# Interface.net
KiCad netlist of a schematic drawn in Altium Designer
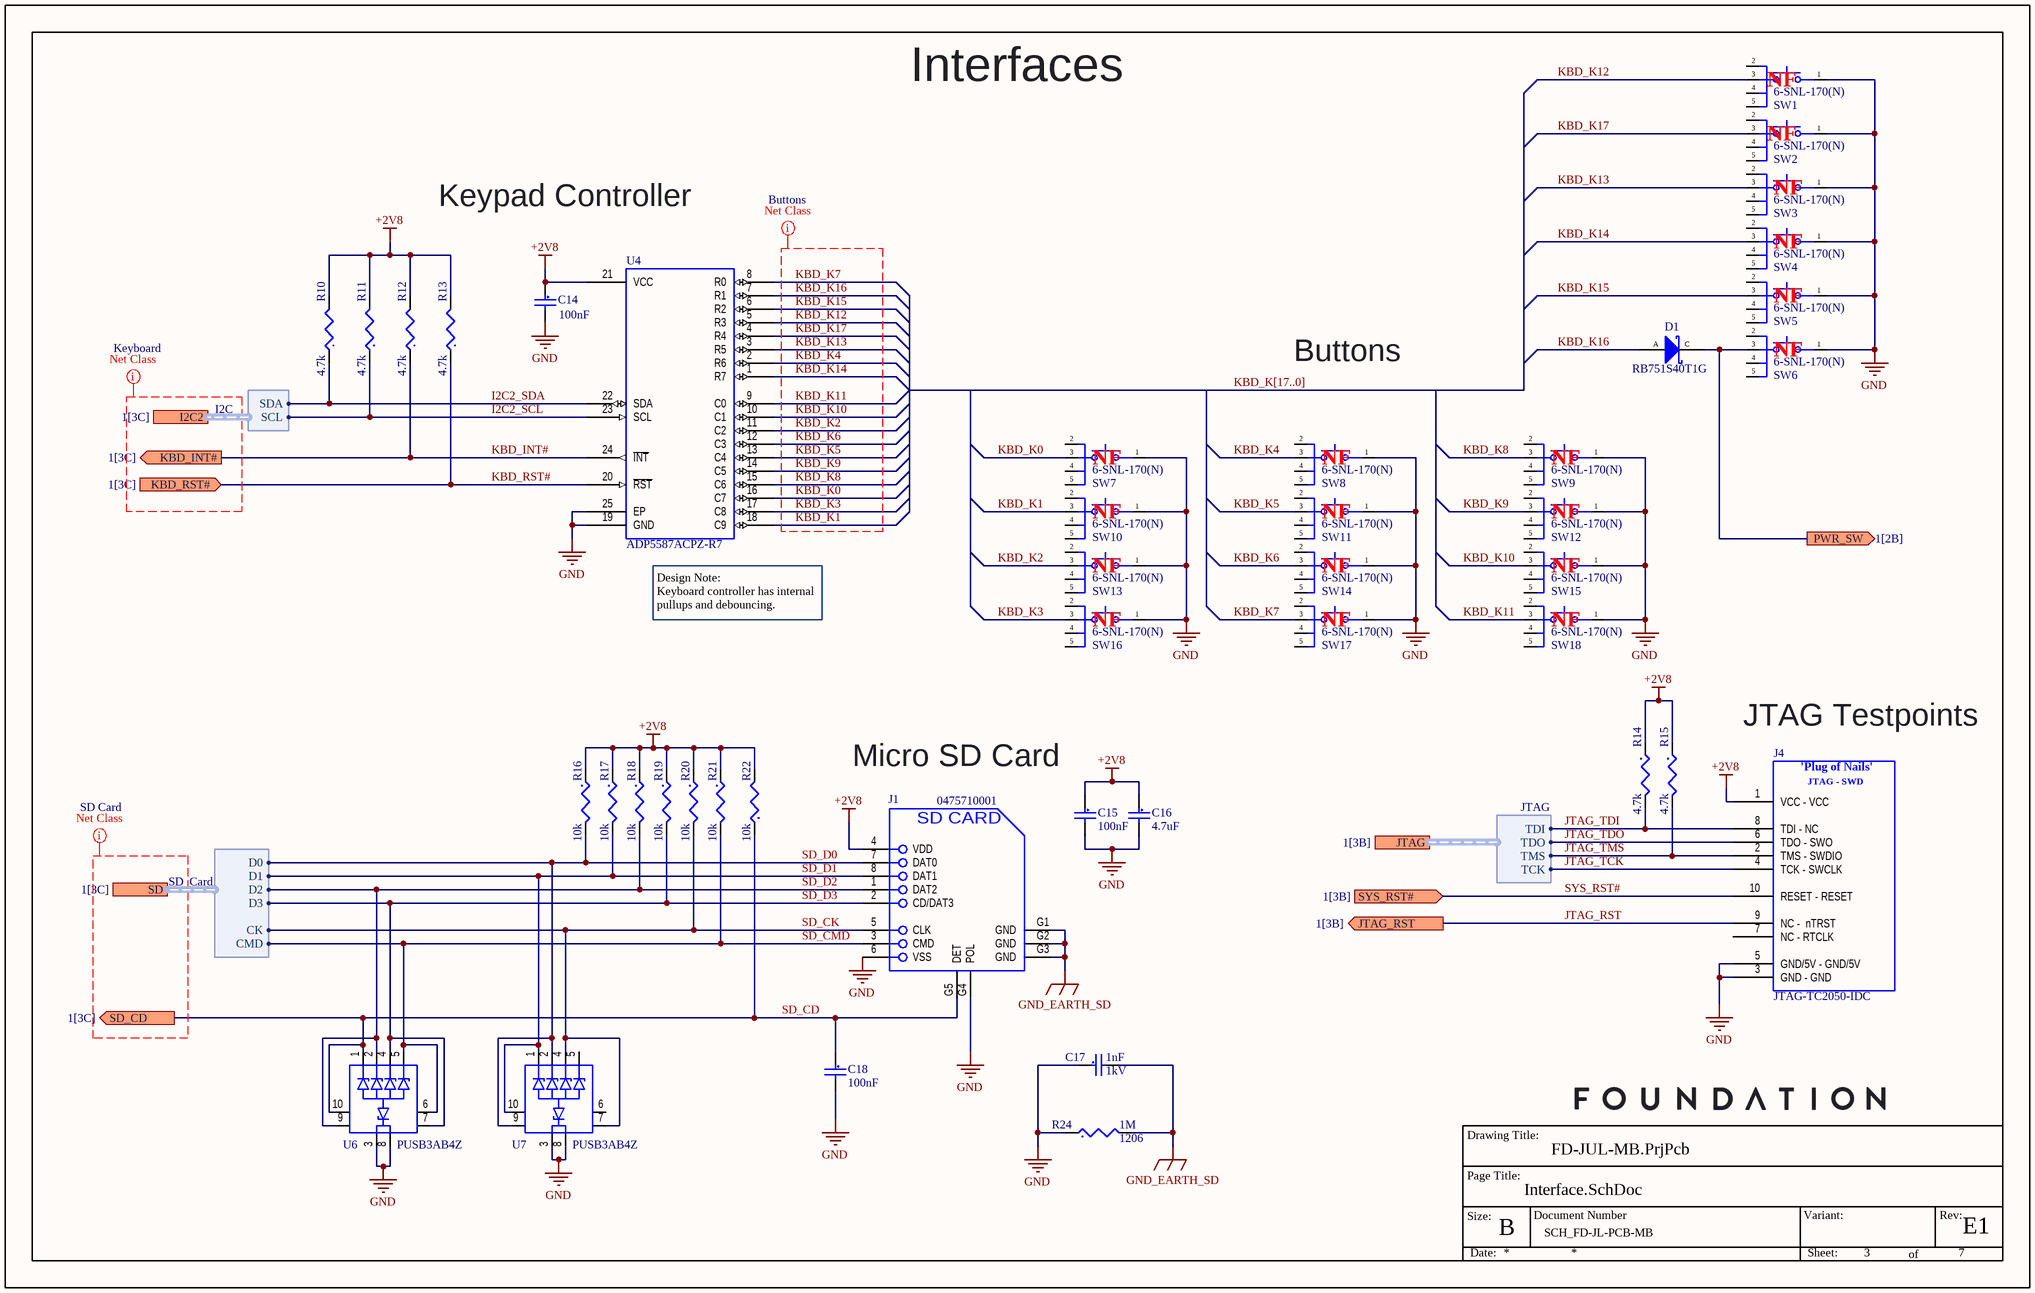
[diagram p0: Interface.SchDoc]

(export (version "E")
  (design (tool "Eeschema 10.0.6"))
  (components
    (comp (ref "C14")
      (value "CAP CER 0.1uF 16V 10% X7R 0402")
      (footprint "CAPC0402(1005)55_L")
      (description "0.1µF ±10% 16V Ceramic Capacitor X7R 0402 (1005 Metric)")
      (fields
        (field (name "CAPACITANCE") "100nF")
        (field (name "TOLERANCE") "10%")
        (field (name "VOLTAGE") "16V")
      )
      (libsource (lib "Altium Concord Pro on A365") (part "CAP-NP-2"))
    )
    (comp (ref "C15")
      (value "CAP CER 0.1uF 16V 10% X7R 0402")
      (footprint "CAPC0402(1005)55_L")
      (description "0.1µF ±10% 16V Ceramic Capacitor X7R 0402 (1005 Metric)")
      (fields
        (field (name "CAPACITANCE") "100nF")
        (field (name "TOLERANCE") "10%")
        (field (name "VOLTAGE") "16V")
      )
      (libsource (lib "Altium Concord Pro on A365") (part "CAP-NP-2"))
    )
    (comp (ref "C16")
      (value "CAP CER 4.7uF 16V 10% X5R 0603")
      (footprint "CAPC0603(1608)90_L")
      (description "4.7µF ±10% 16V Ceramic Capacitor X5R 0603 (1608 Metric)")
      (fields (field (name "CAPACITANCE") "4.7uF") (field (name "TOLERANCE") "10%"))
      (libsource (lib "Altium Concord Pro on A365") (part "CAP-NP-2"))
    )
    (comp (ref "C17")
      (value "CAP CER 1000pF 1000V 10% X7R 0805")
      (footprint "CAPC0805(2012)145_N")
      (description "1000pF ±10% 1000V (1kV) Ceramic Capacitor X7R 0805 (2012 Metric)")
      (fields
        (field (name "CAPACITANCE") "1nF")
        (field (name "VOLTAGE RATING (DC)") "1kV")
        (field (name "TOLERANCE") "10%")
      )
      (libsource (lib "Altium Concord Pro on A365") (part "CAP-NP-2"))
    )
    (comp (ref "C18")
      (value "CAP CER 0.1uF 16V 10% X7R 0402")
      (footprint "CAPC0402(1005)55_L")
      (description "0.1µF ±10% 16V Ceramic Capacitor X7R 0402 (1005 Metric)")
      (fields
        (field (name "CAPACITANCE") "100nF")
        (field (name "TOLERANCE") "10%")
        (field (name "VOLTAGE") "16V")
      )
      (libsource (lib "Altium Concord Pro on A365") (part "CAP-NP-2"))
    )
    (comp (ref "D1")
      (value "RB751S40T1G")
      (footprint "ON - SOD-523_V")
      (description "Diode Schottky 30V 30mA (DC) Surface Mount SOD-523")
      (libsource (lib "Altium Concord Pro on A365") (part "DSKY-AC-2"))
    )
    (comp (ref "J1")
      (value "0475710001")
      (footprint "MOLX - 0475710001_V")
      (description "CONN MICRO SD CARD PUSH-PULL R/A")
      (libsource (lib "Altium Concord Pro on A365") (part "CN-SD-0475710001"))
    )
    (comp (ref "J4")
      (value "JTAG-TC2050-IDC")
      (footprint "TAGC - TC2050-IDC-FP_V")
      (description "PLUG-OF-NAILS 10-PIN W/LEGS")
      (libsource (lib "Altium Concord Pro on A365") (part "JTAG-TC2050-IDC"))
    )
    (comp (ref "R10")
      (value "RES 4.7K 1/16W 1% 0402")
      (footprint "RESC0402(1005)_L")
      (description "4.7 kOhms ±1% 0.063W, 1/16W Chip Resistor 0402 (1005 Metric) Automotive AEC-Q200 Thick Film")
      (fields (field (name "RESISTANCE") "4.7k") (field (name "TOLERANCE") "1%"))
      (libsource (lib "Altium Concord Pro on A365") (part "RES-2"))
    )
    (comp (ref "R11")
      (value "RES 4.7K 1/16W 1% 0402")
      (footprint "RESC0402(1005)_L")
      (description "4.7 kOhms ±1% 0.063W, 1/16W Chip Resistor 0402 (1005 Metric) Automotive AEC-Q200 Thick Film")
      (fields (field (name "RESISTANCE") "4.7k") (field (name "TOLERANCE") "1%"))
      (libsource (lib "Altium Concord Pro on A365") (part "RES-2"))
    )
    (comp (ref "R12")
      (value "RES 4.7K 1/16W 1% 0402")
      (footprint "RESC0402(1005)_L")
      (description "4.7 kOhms ±1% 0.063W, 1/16W Chip Resistor 0402 (1005 Metric) Automotive AEC-Q200 Thick Film")
      (fields (field (name "RESISTANCE") "4.7k") (field (name "TOLERANCE") "1%"))
      (libsource (lib "Altium Concord Pro on A365") (part "RES-2"))
    )
    (comp (ref "R13")
      (value "RES 4.7K 1/16W 1% 0402")
      (footprint "RESC0402(1005)_L")
      (description "4.7 kOhms ±1% 0.063W, 1/16W Chip Resistor 0402 (1005 Metric) Automotive AEC-Q200 Thick Film")
      (fields (field (name "RESISTANCE") "4.7k") (field (name "TOLERANCE") "1%"))
      (libsource (lib "Altium Concord Pro on A365") (part "RES-2"))
    )
    (comp (ref "R14")
      (value "RES 4.7K 1/16W 1% 0402")
      (footprint "RESC0402(1005)_L")
      (description "4.7 kOhms ±1% 0.063W, 1/16W Chip Resistor 0402 (1005 Metric) Automotive AEC-Q200 Thick Film")
      (fields (field (name "RESISTANCE") "4.7k") (field (name "TOLERANCE") "1%"))
      (libsource (lib "Altium Concord Pro on A365") (part "RES-2"))
    )
    (comp (ref "R15")
      (value "RES 4.7K 1/16W 1% 0402")
      (footprint "RESC0402(1005)_L")
      (description "4.7 kOhms ±1% 0.063W, 1/16W Chip Resistor 0402 (1005 Metric) Automotive AEC-Q200 Thick Film")
      (fields (field (name "RESISTANCE") "4.7k") (field (name "TOLERANCE") "1%"))
      (libsource (lib "Altium Concord Pro on A365") (part "RES-2"))
    )
    (comp (ref "R16")
      (value "RES 10K 1/16W 1% 0402")
      (footprint "RESC0402(1005)_L")
      (description "10 kOhms ±1% 0.063W, 1/16W Chip Resistor 0402 (1005 Metric)")
      (fields (field (name "RESISTANCE") "10k") (field (name "TOLERANCE") "1%"))
      (libsource (lib "Altium Concord Pro on A365") (part "RES-2"))
    )
    (comp (ref "R17")
      (value "RES 10K 1/16W 1% 0402")
      (footprint "RESC0402(1005)_L")
      (description "10 kOhms ±1% 0.063W, 1/16W Chip Resistor 0402 (1005 Metric)")
      (fields (field (name "RESISTANCE") "10k") (field (name "TOLERANCE") "1%"))
      (libsource (lib "Altium Concord Pro on A365") (part "RES-2"))
    )
    (comp (ref "R18")
      (value "RES 10K 1/16W 1% 0402")
      (footprint "RESC0402(1005)_L")
      (description "10 kOhms ±1% 0.063W, 1/16W Chip Resistor 0402 (1005 Metric)")
      (fields (field (name "RESISTANCE") "10k") (field (name "TOLERANCE") "1%"))
      (libsource (lib "Altium Concord Pro on A365") (part "RES-2"))
    )
    (comp (ref "R19")
      (value "RES 10K 1/16W 1% 0402")
      (footprint "RESC0402(1005)_L")
      (description "10 kOhms ±1% 0.063W, 1/16W Chip Resistor 0402 (1005 Metric)")
      (fields (field (name "RESISTANCE") "10k") (field (name "TOLERANCE") "1%"))
      (libsource (lib "Altium Concord Pro on A365") (part "RES-2"))
    )
    (comp (ref "R20")
      (value "RES 10K 1/16W 1% 0402")
      (footprint "RESC0402(1005)_L")
      (description "10 kOhms ±1% 0.063W, 1/16W Chip Resistor 0402 (1005 Metric)")
      (fields (field (name "RESISTANCE") "10k") (field (name "TOLERANCE") "1%"))
      (libsource (lib "Altium Concord Pro on A365") (part "RES-2"))
    )
    (comp (ref "R21")
      (value "RES 10K 1/16W 1% 0402")
      (footprint "RESC0402(1005)_L")
      (description "10 kOhms ±1% 0.063W, 1/16W Chip Resistor 0402 (1005 Metric)")
      (fields (field (name "RESISTANCE") "10k") (field (name "TOLERANCE") "1%"))
      (libsource (lib "Altium Concord Pro on A365") (part "RES-2"))
    )
    (comp (ref "R22")
      (value "RES 10K 1/16W 1% 0402")
      (footprint "RESC0402(1005)_L")
      (description "10 kOhms ±1% 0.063W, 1/16W Chip Resistor 0402 (1005 Metric)")
      (fields (field (name "RESISTANCE") "10k") (field (name "TOLERANCE") "1%"))
      (libsource (lib "Altium Concord Pro on A365") (part "RES-2"))
    )
    (comp (ref "R24")
      (value "RES 1.0M 1/4W 5% 1206")
      (footprint "RESC1206(3216)_L")
      (description "1 MOhms ±5% 0.25W, 1/4W Chip Resistor 1206 (3216 Metric) Moisture Resistant Thick Film")
      (fields
        (field (name "RESISTANCE") "1M")
        (field (name "TOLERANCE") "5%")
        (field (name "CASE CODE (IMPERIAL)") "1206")
      )
      (libsource (lib "Altium Concord Pro on A365") (part "RES-2"))
    )
    (comp (ref "SW1")
      (value "6-SNL-170(N)")
      (footprint "TACT - 6-SNL-170_NTP_V")
      (description "Tactile Components. 6mm star dome tactile switch.")
      (libsource (lib "Altium Concord Pro on A365") (part "TAC-2-4"))
    )
    (comp (ref "SW2")
      (value "6-SNL-170(N)")
      (footprint "TACT - 6-SNL-170_NTP_V")
      (description "Tactile Components. 6mm star dome tactile switch.")
      (libsource (lib "Altium Concord Pro on A365") (part "TAC-2-4"))
    )
    (comp (ref "SW3")
      (value "6-SNL-170(N)")
      (footprint "TACT - 6-SNL-170_NTP_V")
      (description "Tactile Components. 6mm star dome tactile switch.")
      (libsource (lib "Altium Concord Pro on A365") (part "TAC-2-4"))
    )
    (comp (ref "SW4")
      (value "6-SNL-170(N)")
      (footprint "TACT - 6-SNL-170_NTP_V")
      (description "Tactile Components. 6mm star dome tactile switch.")
      (libsource (lib "Altium Concord Pro on A365") (part "TAC-2-4"))
    )
    (comp (ref "SW5")
      (value "6-SNL-170(N)")
      (footprint "TACT - 6-SNL-170_NTP_V")
      (description "Tactile Components. 6mm star dome tactile switch.")
      (libsource (lib "Altium Concord Pro on A365") (part "TAC-2-4"))
    )
    (comp (ref "SW6")
      (value "6-SNL-170(N)")
      (footprint "TACT - 6-SNL-170_NTP_V")
      (description "Tactile Components. 6mm star dome tactile switch.")
      (libsource (lib "Altium Concord Pro on A365") (part "TAC-2-4"))
    )
    (comp (ref "SW7")
      (value "6-SNL-170(N)")
      (footprint "TACT - 6-SNL-170_NTP_V")
      (description "Tactile Components. 6mm star dome tactile switch.")
      (libsource (lib "Altium Concord Pro on A365") (part "TAC-2-4"))
    )
    (comp (ref "SW8")
      (value "6-SNL-170(N)")
      (footprint "TACT - 6-SNL-170_NTP_V")
      (description "Tactile Components. 6mm star dome tactile switch.")
      (libsource (lib "Altium Concord Pro on A365") (part "TAC-2-4"))
    )
    (comp (ref "SW9")
      (value "6-SNL-170(N)")
      (footprint "TACT - 6-SNL-170_NTP_V")
      (description "Tactile Components. 6mm star dome tactile switch.")
      (libsource (lib "Altium Concord Pro on A365") (part "TAC-2-4"))
    )
    (comp (ref "SW10")
      (value "6-SNL-170(N)")
      (footprint "TACT - 6-SNL-170_NTP_V")
      (description "Tactile Components. 6mm star dome tactile switch.")
      (libsource (lib "Altium Concord Pro on A365") (part "TAC-2-4"))
    )
    (comp (ref "SW11")
      (value "6-SNL-170(N)")
      (footprint "TACT - 6-SNL-170_NTP_V")
      (description "Tactile Components. 6mm star dome tactile switch.")
      (libsource (lib "Altium Concord Pro on A365") (part "TAC-2-4"))
    )
    (comp (ref "SW12")
      (value "6-SNL-170(N)")
      (footprint "TACT - 6-SNL-170_NTP_V")
      (description "Tactile Components. 6mm star dome tactile switch.")
      (libsource (lib "Altium Concord Pro on A365") (part "TAC-2-4"))
    )
    (comp (ref "SW13")
      (value "6-SNL-170(N)")
      (footprint "TACT - 6-SNL-170_NTP_V")
      (description "Tactile Components. 6mm star dome tactile switch.")
      (libsource (lib "Altium Concord Pro on A365") (part "TAC-2-4"))
    )
    (comp (ref "SW14")
      (value "6-SNL-170(N)")
      (footprint "TACT - 6-SNL-170_NTP_V")
      (description "Tactile Components. 6mm star dome tactile switch.")
      (libsource (lib "Altium Concord Pro on A365") (part "TAC-2-4"))
    )
    (comp (ref "SW15")
      (value "6-SNL-170(N)")
      (footprint "TACT - 6-SNL-170_NTP_V")
      (description "Tactile Components. 6mm star dome tactile switch.")
      (libsource (lib "Altium Concord Pro on A365") (part "TAC-2-4"))
    )
    (comp (ref "SW16")
      (value "6-SNL-170(N)")
      (footprint "TACT - 6-SNL-170_NTP_V")
      (description "Tactile Components. 6mm star dome tactile switch.")
      (libsource (lib "Altium Concord Pro on A365") (part "TAC-2-4"))
    )
    (comp (ref "SW17")
      (value "6-SNL-170(N)")
      (footprint "TACT - 6-SNL-170_NTP_V")
      (description "Tactile Components. 6mm star dome tactile switch.")
      (libsource (lib "Altium Concord Pro on A365") (part "TAC-2-4"))
    )
    (comp (ref "SW18")
      (value "6-SNL-170(N)")
      (footprint "TACT - 6-SNL-170_NTP_V")
      (description "Tactile Components. 6mm star dome tactile switch.")
      (libsource (lib "Altium Concord Pro on A365") (part "TAC-2-4"))
    )
    (comp (ref "U4")
      (value "ADP5587ACPZ-R7")
      (footprint "ADEV - LFCSP-24_L")
      (description "I/O Expander 18 I²C 400kHz 24-LFCSP-WQ (4x4)")
      (libsource (lib "Altium Concord Pro on A365") (part "ADP5587ACPZ"))
    )
    (comp (ref "U6")
      (value "PUSB3AB4Z")
      (footprint "NEXP - DFN2510A-10_L")
      (description "TVS DIODE 3.3V 5V DFN2510A-10")
      (libsource (lib "Altium Concord Pro on A365") (part "DTVS-ARY-4-1245-8-10"))
    )
    (comp (ref "U7")
      (value "PUSB3AB4Z")
      (footprint "NEXP - DFN2510A-10_L")
      (description "TVS DIODE 3.3V 5V DFN2510A-10")
      (libsource (lib "Altium Concord Pro on A365") (part "DTVS-ARY-4-1245-8-10"))
    )
  )
  (nets
    (net (code "4") (name "+2V8") (class "Default")
      (node (ref "C14") (pin "1") (pinfunction "1_1") (pintype "passive"))
      (node (ref "C15") (pin "1") (pinfunction "1_1") (pintype "passive"))
      (node (ref "C16") (pin "1") (pinfunction "1_1") (pintype "passive"))
      (node (ref "J1") (pin "4") (pinfunction "VDD_4") (pintype "passive"))
      (node (ref "J4") (pin "1") (pinfunction "VCC_-_VCC_1") (pintype "passive"))
      (node (ref "R10") (pin "2") (pinfunction "2_2") (pintype "passive"))
      (node (ref "R11") (pin "2") (pinfunction "2_2") (pintype "passive"))
      (node (ref "R12") (pin "2") (pinfunction "2_2") (pintype "passive"))
      (node (ref "R13") (pin "2") (pinfunction "2_2") (pintype "passive"))
      (node (ref "R14") (pin "1") (pinfunction "1_1") (pintype "passive"))
      (node (ref "R15") (pin "1") (pinfunction "1_1") (pintype "passive"))
      (node (ref "R16") (pin "1") (pinfunction "1_1") (pintype "passive"))
      (node (ref "R17") (pin "1") (pinfunction "1_1") (pintype "passive"))
      (node (ref "R18") (pin "1") (pinfunction "1_1") (pintype "passive"))
      (node (ref "R19") (pin "1") (pinfunction "1_1") (pintype "passive"))
      (node (ref "R20") (pin "1") (pinfunction "1_1") (pintype "passive"))
      (node (ref "R21") (pin "1") (pinfunction "1_1") (pintype "passive"))
      (node (ref "R22") (pin "2") (pinfunction "2_2") (pintype "passive"))
      (node (ref "U4") (pin "21") (pinfunction "VCC_21") (pintype "power_in"))
    )
    (net (code "5") (name "/I2C2_SCL") (class "Default")
      (node (ref "R11") (pin "1") (pinfunction "1_1") (pintype "passive"))
      (node (ref "U4") (pin "23") (pinfunction "SCL_23") (pintype "input"))
    )
    (net (code "6") (name "/I2C2_SDA") (class "Default")
      (node (ref "R10") (pin "1") (pinfunction "1_1") (pintype "passive"))
      (node (ref "U4") (pin "22") (pinfunction "SDA_22") (pintype "bidirectional"))
    )
    (net (code "7") (name "/JTAG_RST") (class "Default")
      (node (ref "J4") (pin "9") (pinfunction "NC_-__nTRST_9") (pintype "passive"))
    )
    (net (code "8") (name "/JTAG_TCK") (class "Default")
      (node (ref "J4") (pin "4") (pinfunction "TCK_-_SWCLK_4") (pintype "passive"))
    )
    (net (code "9") (name "/JTAG_TDI") (class "Default")
      (node (ref "J4") (pin "8") (pinfunction "TDI_-_NC_8") (pintype "passive"))
      (node (ref "R14") (pin "2") (pinfunction "2_2") (pintype "passive"))
    )
    (net (code "10") (name "/JTAG_TDO") (class "Default")
      (node (ref "J4") (pin "6") (pinfunction "TDO_-_SWO_6") (pintype "passive"))
    )
    (net (code "11") (name "/JTAG_TMS") (class "Default")
      (node (ref "J4") (pin "2") (pinfunction "TMS_-_SWDIO_2") (pintype "passive"))
      (node (ref "R15") (pin "2") (pinfunction "2_2") (pintype "passive"))
    )
    (net (code "12") (name "/KBD_INT#") (class "Default")
      (node (ref "R12") (pin "1") (pinfunction "1_1") (pintype "passive"))
      (node (ref "U4") (pin "24") (pinfunction "~{INT}_24") (pintype "output"))
    )
    (net (code "13") (name "/KBD_K0") (class "Default")
      (node (ref "SW7") (pin "3") (pinfunction "3_3") (pintype "passive"))
      (node (ref "U4") (pin "16") (pinfunction "C7_16") (pintype "bidirectional"))
    )
    (net (code "14") (name "/KBD_K1") (class "Default")
      (node (ref "SW10") (pin "3") (pinfunction "3_3") (pintype "passive"))
      (node (ref "U4") (pin "18") (pinfunction "C9_18") (pintype "bidirectional"))
    )
    (net (code "15") (name "/KBD_K2") (class "Default")
      (node (ref "SW13") (pin "3") (pinfunction "3_3") (pintype "passive"))
      (node (ref "U4") (pin "11") (pinfunction "C2_11") (pintype "bidirectional"))
    )
    (net (code "16") (name "/KBD_K3") (class "Default")
      (node (ref "SW16") (pin "3") (pinfunction "3_3") (pintype "passive"))
      (node (ref "U4") (pin "17") (pinfunction "C8_17") (pintype "bidirectional"))
    )
    (net (code "17") (name "/KBD_K4") (class "Default")
      (node (ref "SW8") (pin "3") (pinfunction "3_3") (pintype "passive"))
      (node (ref "U4") (pin "2") (pinfunction "R6_2") (pintype "bidirectional"))
    )
    (net (code "18") (name "/KBD_K5") (class "Default")
      (node (ref "SW11") (pin "3") (pinfunction "3_3") (pintype "passive"))
      (node (ref "U4") (pin "13") (pinfunction "C4_13") (pintype "bidirectional"))
    )
    (net (code "19") (name "/KBD_K6") (class "Default")
      (node (ref "SW14") (pin "3") (pinfunction "3_3") (pintype "passive"))
      (node (ref "U4") (pin "12") (pinfunction "C3_12") (pintype "bidirectional"))
    )
    (net (code "20") (name "/KBD_K7") (class "Default")
      (node (ref "SW17") (pin "3") (pinfunction "3_3") (pintype "passive"))
      (node (ref "U4") (pin "8") (pinfunction "R0_8") (pintype "bidirectional"))
    )
    (net (code "21") (name "/KBD_K8") (class "Default")
      (node (ref "SW9") (pin "3") (pinfunction "3_3") (pintype "passive"))
      (node (ref "U4") (pin "15") (pinfunction "C6_15") (pintype "bidirectional"))
    )
    (net (code "22") (name "/KBD_K9") (class "Default")
      (node (ref "SW12") (pin "3") (pinfunction "3_3") (pintype "passive"))
      (node (ref "U4") (pin "14") (pinfunction "C5_14") (pintype "bidirectional"))
    )
    (net (code "23") (name "/KBD_K10") (class "Default")
      (node (ref "SW15") (pin "3") (pinfunction "3_3") (pintype "passive"))
      (node (ref "U4") (pin "10") (pinfunction "C1_10") (pintype "bidirectional"))
    )
    (net (code "24") (name "/KBD_K11") (class "Default")
      (node (ref "SW18") (pin "3") (pinfunction "3_3") (pintype "passive"))
      (node (ref "U4") (pin "9") (pinfunction "C0_9") (pintype "bidirectional"))
    )
    (net (code "25") (name "/KBD_K12") (class "Default")
      (node (ref "SW1") (pin "3") (pinfunction "3_3") (pintype "passive"))
      (node (ref "U4") (pin "5") (pinfunction "R3_5") (pintype "bidirectional"))
    )
    (net (code "26") (name "/KBD_K13") (class "Default")
      (node (ref "SW3") (pin "3") (pinfunction "3_3") (pintype "passive"))
      (node (ref "U4") (pin "3") (pinfunction "R5_3") (pintype "bidirectional"))
    )
    (net (code "27") (name "/KBD_K14") (class "Default")
      (node (ref "SW4") (pin "3") (pinfunction "3_3") (pintype "passive"))
      (node (ref "U4") (pin "1") (pinfunction "R7_1") (pintype "bidirectional"))
    )
    (net (code "28") (name "/KBD_K15") (class "Default")
      (node (ref "SW5") (pin "3") (pinfunction "3_3") (pintype "passive"))
      (node (ref "U4") (pin "6") (pinfunction "R2_6") (pintype "bidirectional"))
    )
    (net (code "29") (name "/KBD_K16") (class "Default")
      (node (ref "D1") (pin "A") (pinfunction "A_A") (pintype "passive"))
      (node (ref "U4") (pin "7") (pinfunction "R1_7") (pintype "bidirectional"))
    )
    (net (code "30") (name "/KBD_K17") (class "Default")
      (node (ref "SW2") (pin "3") (pinfunction "3_3") (pintype "passive"))
      (node (ref "U4") (pin "4") (pinfunction "R4_4") (pintype "bidirectional"))
    )
    (net (code "32") (name "/KBD_RST#") (class "Default")
      (node (ref "R13") (pin "1") (pinfunction "1_1") (pintype "passive"))
      (node (ref "U4") (pin "20") (pinfunction "~{RST}_20") (pintype "input"))
    )
    (net (code "33") (name "/PWR_SW") (class "Default")
      (node (ref "D1") (pin "C") (pinfunction "C_C") (pintype "passive"))
      (node (ref "SW6") (pin "3") (pinfunction "3_3") (pintype "passive"))
    )
    (net (code "34") (name "/SD_CD") (class "Default")
      (node (ref "C18") (pin "1") (pinfunction "1_1") (pintype "passive"))
      (node (ref "J1") (pin "G5") (pinfunction "DET_G5") (pintype "passive"))
      (node (ref "R22") (pin "1") (pinfunction "1_1") (pintype "passive"))
      (node (ref "U6") (pin "1") (pinfunction "DIODE_1") (pintype "passive"))
      (node (ref "U6") (pin "10") (pinfunction "DIODE_10") (pintype "passive"))
    )
    (net (code "35") (name "/SD_CK") (class "Default")
      (node (ref "J1") (pin "5") (pinfunction "CLK_5") (pintype "passive"))
      (node (ref "R20") (pin "2") (pinfunction "2_2") (pintype "passive"))
      (node (ref "U7") (pin "4") (pinfunction "DIODE_4") (pintype "passive"))
      (node (ref "U7") (pin "7") (pinfunction "DIODE_7") (pintype "passive"))
    )
    (net (code "36") (name "/SD_CMD") (class "Default")
      (node (ref "J1") (pin "3") (pinfunction "CMD_3") (pintype "passive"))
      (node (ref "R21") (pin "2") (pinfunction "2_2") (pintype "passive"))
      (node (ref "U6") (pin "5") (pinfunction "DIODE_5") (pintype "passive"))
      (node (ref "U6") (pin "6") (pinfunction "DIODE_6") (pintype "passive"))
    )
    (net (code "37") (name "/SD_D0") (class "Default")
      (node (ref "J1") (pin "7") (pinfunction "DAT0_7") (pintype "passive"))
      (node (ref "R16") (pin "2") (pinfunction "2_2") (pintype "passive"))
      (node (ref "U7") (pin "2") (pinfunction "A_2") (pintype "passive"))
      (node (ref "U7") (pin "9") (pinfunction "DIODE_9") (pintype "passive"))
    )
    (net (code "38") (name "/SD_D1") (class "Default")
      (node (ref "J1") (pin "8") (pinfunction "DAT1_8") (pintype "passive"))
      (node (ref "R17") (pin "2") (pinfunction "2_2") (pintype "passive"))
      (node (ref "U7") (pin "1") (pinfunction "DIODE_1") (pintype "passive"))
      (node (ref "U7") (pin "10") (pinfunction "DIODE_10") (pintype "passive"))
    )
    (net (code "39") (name "/SD_D2") (class "Default")
      (node (ref "J1") (pin "1") (pinfunction "DAT2_1") (pintype "passive"))
      (node (ref "R18") (pin "2") (pinfunction "2_2") (pintype "passive"))
      (node (ref "U6") (pin "2") (pinfunction "A_2") (pintype "passive"))
      (node (ref "U6") (pin "9") (pinfunction "DIODE_9") (pintype "passive"))
    )
    (net (code "40") (name "/SD_D3") (class "Default")
      (node (ref "J1") (pin "2") (pinfunction "CD/DAT3_2") (pintype "passive"))
      (node (ref "R19") (pin "2") (pinfunction "2_2") (pintype "passive"))
      (node (ref "U6") (pin "4") (pinfunction "DIODE_4") (pintype "passive"))
      (node (ref "U6") (pin "7") (pinfunction "DIODE_7") (pintype "passive"))
    )
    (net (code "41") (name "/SYS_RST#") (class "Default")
      (node (ref "J4") (pin "10") (pinfunction "RESET_-_RESET_10") (pintype "passive"))
    )
    (net (code "45") (name "GND") (class "Default")
      (node (ref "C14") (pin "2") (pinfunction "2_2") (pintype "passive"))
      (node (ref "C15") (pin "2") (pinfunction "2_2") (pintype "passive"))
      (node (ref "C16") (pin "2") (pinfunction "2_2") (pintype "passive"))
      (node (ref "C17") (pin "1") (pinfunction "1_1") (pintype "passive"))
      (node (ref "C18") (pin "2") (pinfunction "2_2") (pintype "passive"))
      (node (ref "J1") (pin "6") (pinfunction "VSS_6") (pintype "passive"))
      (node (ref "J1") (pin "G4") (pinfunction "POL_G4") (pintype "passive"))
      (node (ref "J4") (pin "3") (pinfunction "GND_-_GND_3") (pintype "passive"))
      (node (ref "J4") (pin "5") (pinfunction "GND/5V_-_GND/5V_5") (pintype "passive"))
      (node (ref "R24") (pin "1") (pinfunction "1_1") (pintype "passive"))
      (node (ref "SW1") (pin "1") (pinfunction "1_1") (pintype "passive"))
      (node (ref "SW10") (pin "1") (pinfunction "1_1") (pintype "passive"))
      (node (ref "SW11") (pin "1") (pinfunction "1_1") (pintype "passive"))
      (node (ref "SW12") (pin "1") (pinfunction "1_1") (pintype "passive"))
      (node (ref "SW13") (pin "1") (pinfunction "1_1") (pintype "passive"))
      (node (ref "SW14") (pin "1") (pinfunction "1_1") (pintype "passive"))
      (node (ref "SW15") (pin "1") (pinfunction "1_1") (pintype "passive"))
      (node (ref "SW16") (pin "1") (pinfunction "1_1") (pintype "passive"))
      (node (ref "SW17") (pin "1") (pinfunction "1_1") (pintype "passive"))
      (node (ref "SW18") (pin "1") (pinfunction "1_1") (pintype "passive"))
      (node (ref "SW2") (pin "1") (pinfunction "1_1") (pintype "passive"))
      (node (ref "SW3") (pin "1") (pinfunction "1_1") (pintype "passive"))
      (node (ref "SW4") (pin "1") (pinfunction "1_1") (pintype "passive"))
      (node (ref "SW5") (pin "1") (pinfunction "1_1") (pintype "passive"))
      (node (ref "SW6") (pin "1") (pinfunction "1_1") (pintype "passive"))
      (node (ref "SW7") (pin "1") (pinfunction "1_1") (pintype "passive"))
      (node (ref "SW8") (pin "1") (pinfunction "1_1") (pintype "passive"))
      (node (ref "SW9") (pin "1") (pinfunction "1_1") (pintype "passive"))
      (node (ref "U4") (pin "19") (pinfunction "GND_19") (pintype "power_in"))
      (node (ref "U4") (pin "25") (pinfunction "EP_25") (pintype "power_in"))
      (node (ref "U6") (pin "3") (pinfunction "DIODE_3") (pintype "passive"))
      (node (ref "U6") (pin "8") (pinfunction "DIODE_8") (pintype "passive"))
      (node (ref "U7") (pin "3") (pinfunction "DIODE_3") (pintype "passive"))
      (node (ref "U7") (pin "8") (pinfunction "DIODE_8") (pintype "passive"))
    )
    (net (code "46") (name "GND_EARTH_SD") (class "Default")
      (node (ref "C17") (pin "2") (pinfunction "2_2") (pintype "passive"))
      (node (ref "J1") (pin "G1") (pinfunction "GND_G1") (pintype "passive"))
      (node (ref "J1") (pin "G2") (pinfunction "GND_G2") (pintype "passive"))
      (node (ref "J1") (pin "G3") (pinfunction "GND_G3") (pintype "passive"))
      (node (ref "R24") (pin "2") (pinfunction "2_2") (pintype "passive"))
    )
    (net (code "47") (name "unconnected-(J4-NC_-_RTCLK-Pad7)") (class "Default")
      (node (ref "J4") (pin "7") (pinfunction "NC_-_RTCLK_7") (pintype "passive"))
    )
    (net (code "48") (name "unconnected-(SW1-Pad2)") (class "Default")
      (node (ref "SW1") (pin "2") (pinfunction "2_2") (pintype "passive"))
    )
    (net (code "49") (name "unconnected-(SW1-Pad4)") (class "Default")
      (node (ref "SW1") (pin "4") (pinfunction "4_4") (pintype "passive"))
    )
    (net (code "50") (name "unconnected-(SW1-Pad5)") (class "Default")
      (node (ref "SW1") (pin "5") (pinfunction "5_5") (pintype "passive"))
    )
    (net (code "51") (name "unconnected-(SW2-Pad2)") (class "Default")
      (node (ref "SW2") (pin "2") (pinfunction "2_2") (pintype "passive"))
    )
    (net (code "52") (name "unconnected-(SW2-Pad4)") (class "Default")
      (node (ref "SW2") (pin "4") (pinfunction "4_4") (pintype "passive"))
    )
    (net (code "53") (name "unconnected-(SW2-Pad5)") (class "Default")
      (node (ref "SW2") (pin "5") (pinfunction "5_5") (pintype "passive"))
    )
    (net (code "54") (name "unconnected-(SW3-Pad2)") (class "Default")
      (node (ref "SW3") (pin "2") (pinfunction "2_2") (pintype "passive"))
    )
    (net (code "55") (name "unconnected-(SW3-Pad4)") (class "Default")
      (node (ref "SW3") (pin "4") (pinfunction "4_4") (pintype "passive"))
    )
    (net (code "56") (name "unconnected-(SW3-Pad5)") (class "Default")
      (node (ref "SW3") (pin "5") (pinfunction "5_5") (pintype "passive"))
    )
    (net (code "57") (name "unconnected-(SW4-Pad2)") (class "Default")
      (node (ref "SW4") (pin "2") (pinfunction "2_2") (pintype "passive"))
    )
    (net (code "58") (name "unconnected-(SW4-Pad4)") (class "Default")
      (node (ref "SW4") (pin "4") (pinfunction "4_4") (pintype "passive"))
    )
    (net (code "59") (name "unconnected-(SW4-Pad5)") (class "Default")
      (node (ref "SW4") (pin "5") (pinfunction "5_5") (pintype "passive"))
    )
    (net (code "60") (name "unconnected-(SW5-Pad2)") (class "Default")
      (node (ref "SW5") (pin "2") (pinfunction "2_2") (pintype "passive"))
    )
    (net (code "61") (name "unconnected-(SW5-Pad4)") (class "Default")
      (node (ref "SW5") (pin "4") (pinfunction "4_4") (pintype "passive"))
    )
    (net (code "62") (name "unconnected-(SW5-Pad5)") (class "Default")
      (node (ref "SW5") (pin "5") (pinfunction "5_5") (pintype "passive"))
    )
    (net (code "63") (name "unconnected-(SW6-Pad2)") (class "Default")
      (node (ref "SW6") (pin "2") (pinfunction "2_2") (pintype "passive"))
    )
    (net (code "64") (name "unconnected-(SW6-Pad4)") (class "Default")
      (node (ref "SW6") (pin "4") (pinfunction "4_4") (pintype "passive"))
    )
    (net (code "65") (name "unconnected-(SW6-Pad5)") (class "Default")
      (node (ref "SW6") (pin "5") (pinfunction "5_5") (pintype "passive"))
    )
    (net (code "66") (name "unconnected-(SW7-Pad2)") (class "Default")
      (node (ref "SW7") (pin "2") (pinfunction "2_2") (pintype "passive"))
    )
    (net (code "67") (name "unconnected-(SW7-Pad4)") (class "Default")
      (node (ref "SW7") (pin "4") (pinfunction "4_4") (pintype "passive"))
    )
    (net (code "68") (name "unconnected-(SW7-Pad5)") (class "Default")
      (node (ref "SW7") (pin "5") (pinfunction "5_5") (pintype "passive"))
    )
    (net (code "69") (name "unconnected-(SW8-Pad2)") (class "Default")
      (node (ref "SW8") (pin "2") (pinfunction "2_2") (pintype "passive"))
    )
    (net (code "70") (name "unconnected-(SW8-Pad4)") (class "Default")
      (node (ref "SW8") (pin "4") (pinfunction "4_4") (pintype "passive"))
    )
    (net (code "71") (name "unconnected-(SW8-Pad5)") (class "Default")
      (node (ref "SW8") (pin "5") (pinfunction "5_5") (pintype "passive"))
    )
    (net (code "72") (name "unconnected-(SW9-Pad2)") (class "Default")
      (node (ref "SW9") (pin "2") (pinfunction "2_2") (pintype "passive"))
    )
    (net (code "73") (name "unconnected-(SW9-Pad4)") (class "Default")
      (node (ref "SW9") (pin "4") (pinfunction "4_4") (pintype "passive"))
    )
    (net (code "74") (name "unconnected-(SW9-Pad5)") (class "Default")
      (node (ref "SW9") (pin "5") (pinfunction "5_5") (pintype "passive"))
    )
    (net (code "75") (name "unconnected-(SW10-Pad2)") (class "Default")
      (node (ref "SW10") (pin "2") (pinfunction "2_2") (pintype "passive"))
    )
    (net (code "76") (name "unconnected-(SW10-Pad4)") (class "Default")
      (node (ref "SW10") (pin "4") (pinfunction "4_4") (pintype "passive"))
    )
    (net (code "77") (name "unconnected-(SW10-Pad5)") (class "Default")
      (node (ref "SW10") (pin "5") (pinfunction "5_5") (pintype "passive"))
    )
    (net (code "78") (name "unconnected-(SW11-Pad2)") (class "Default")
      (node (ref "SW11") (pin "2") (pinfunction "2_2") (pintype "passive"))
    )
    (net (code "79") (name "unconnected-(SW11-Pad4)") (class "Default")
      (node (ref "SW11") (pin "4") (pinfunction "4_4") (pintype "passive"))
    )
    (net (code "80") (name "unconnected-(SW11-Pad5)") (class "Default")
      (node (ref "SW11") (pin "5") (pinfunction "5_5") (pintype "passive"))
    )
    (net (code "81") (name "unconnected-(SW12-Pad2)") (class "Default")
      (node (ref "SW12") (pin "2") (pinfunction "2_2") (pintype "passive"))
    )
    (net (code "82") (name "unconnected-(SW12-Pad4)") (class "Default")
      (node (ref "SW12") (pin "4") (pinfunction "4_4") (pintype "passive"))
    )
    (net (code "83") (name "unconnected-(SW12-Pad5)") (class "Default")
      (node (ref "SW12") (pin "5") (pinfunction "5_5") (pintype "passive"))
    )
    (net (code "84") (name "unconnected-(SW13-Pad2)") (class "Default")
      (node (ref "SW13") (pin "2") (pinfunction "2_2") (pintype "passive"))
    )
    (net (code "85") (name "unconnected-(SW13-Pad4)") (class "Default")
      (node (ref "SW13") (pin "4") (pinfunction "4_4") (pintype "passive"))
    )
    (net (code "86") (name "unconnected-(SW13-Pad5)") (class "Default")
      (node (ref "SW13") (pin "5") (pinfunction "5_5") (pintype "passive"))
    )
    (net (code "87") (name "unconnected-(SW14-Pad2)") (class "Default")
      (node (ref "SW14") (pin "2") (pinfunction "2_2") (pintype "passive"))
    )
    (net (code "88") (name "unconnected-(SW14-Pad4)") (class "Default")
      (node (ref "SW14") (pin "4") (pinfunction "4_4") (pintype "passive"))
    )
    (net (code "89") (name "unconnected-(SW14-Pad5)") (class "Default")
      (node (ref "SW14") (pin "5") (pinfunction "5_5") (pintype "passive"))
    )
    (net (code "90") (name "unconnected-(SW15-Pad2)") (class "Default")
      (node (ref "SW15") (pin "2") (pinfunction "2_2") (pintype "passive"))
    )
    (net (code "91") (name "unconnected-(SW15-Pad4)") (class "Default")
      (node (ref "SW15") (pin "4") (pinfunction "4_4") (pintype "passive"))
    )
    (net (code "92") (name "unconnected-(SW15-Pad5)") (class "Default")
      (node (ref "SW15") (pin "5") (pinfunction "5_5") (pintype "passive"))
    )
    (net (code "93") (name "unconnected-(SW16-Pad2)") (class "Default")
      (node (ref "SW16") (pin "2") (pinfunction "2_2") (pintype "passive"))
    )
    (net (code "94") (name "unconnected-(SW16-Pad4)") (class "Default")
      (node (ref "SW16") (pin "4") (pinfunction "4_4") (pintype "passive"))
    )
    (net (code "95") (name "unconnected-(SW16-Pad5)") (class "Default")
      (node (ref "SW16") (pin "5") (pinfunction "5_5") (pintype "passive"))
    )
    (net (code "96") (name "unconnected-(SW17-Pad2)") (class "Default")
      (node (ref "SW17") (pin "2") (pinfunction "2_2") (pintype "passive"))
    )
    (net (code "97") (name "unconnected-(SW17-Pad4)") (class "Default")
      (node (ref "SW17") (pin "4") (pinfunction "4_4") (pintype "passive"))
    )
    (net (code "98") (name "unconnected-(SW17-Pad5)") (class "Default")
      (node (ref "SW17") (pin "5") (pinfunction "5_5") (pintype "passive"))
    )
    (net (code "99") (name "unconnected-(SW18-Pad2)") (class "Default")
      (node (ref "SW18") (pin "2") (pinfunction "2_2") (pintype "passive"))
    )
    (net (code "100") (name "unconnected-(SW18-Pad4)") (class "Default")
      (node (ref "SW18") (pin "4") (pinfunction "4_4") (pintype "passive"))
    )
    (net (code "101") (name "unconnected-(SW18-Pad5)") (class "Default")
      (node (ref "SW18") (pin "5") (pinfunction "5_5") (pintype "passive"))
    )
    (net (code "102") (name "unconnected-(U7-DIODE-Pad5)") (class "Default")
      (node (ref "U7") (pin "5") (pinfunction "DIODE_5") (pintype "passive"))
    )
    (net (code "103") (name "unconnected-(U7-DIODE-Pad6)") (class "Default")
      (node (ref "U7") (pin "6") (pinfunction "DIODE_6") (pintype "passive"))
    )
  )
)
